# ProDoc_Sensor_2025-09-14.net
KiCad netlist of a schematic drawn in EasyEDA Pro
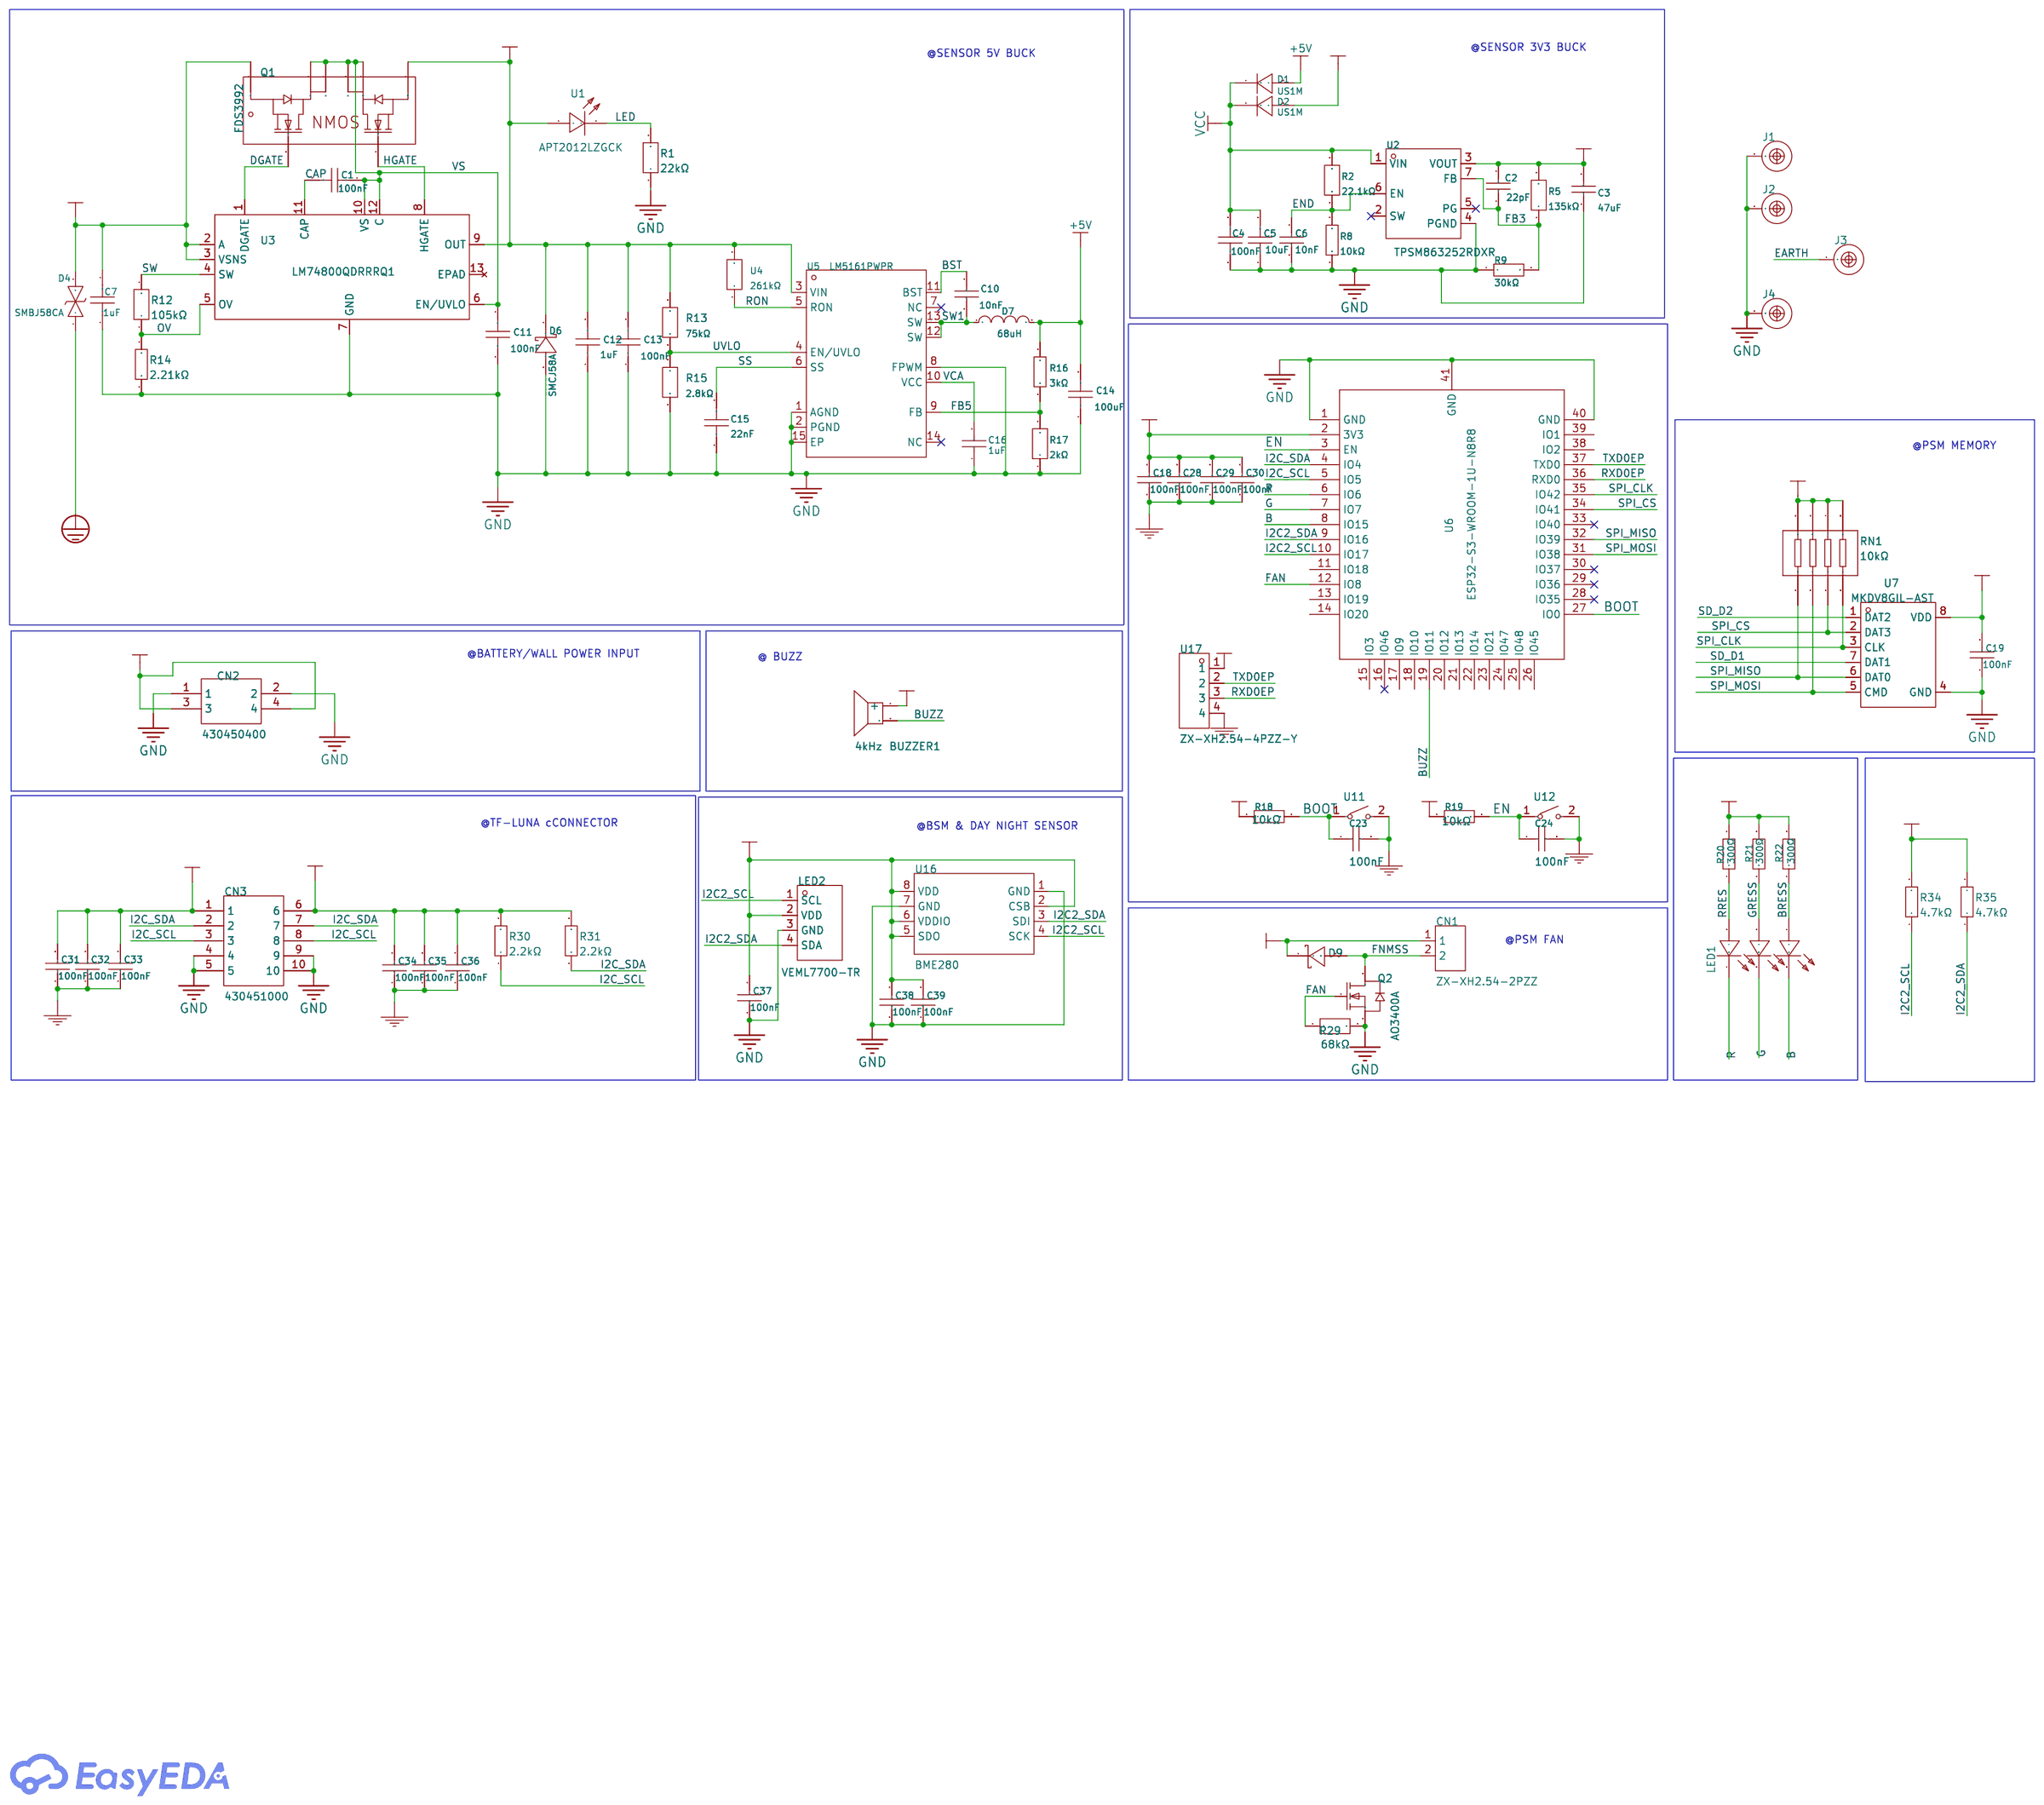
[diagram p0: schematic sheet]

(export (version "E")
  (design (tool "Eeschema 10.0.6"))
  (components
    (comp (ref "BUZZER1")
      (value "4kHz")
      (footprint "easyedapro:BUZ-TH_PKM13EPYH4002-B0")
      (fields
        (field (name "Manufacturer Part") "PKM13EPYH4002-B0")
        (field (name "Manufacturer") "muRata(村田)")
      )
      (libsource (lib "easyedapro") (part "PKM13EPYH4002-B0"))
    )
    (comp (ref "C1")
      (value "100nF")
      (footprint "easyedapro:C1210")
      (fields
        (field (name "Manufacturer Part") "CC1210KKX7RYBB104")
        (field (name "Manufacturer") "YAGEO(国巨)")
      )
      (libsource (lib "easyedapro") (part "CC1210KKX7RYBB104"))
    )
    (comp (ref "C2")
      (value "22pF")
      (footprint "easyedapro:C0201")
      (fields
        (field (name "Manufacturer Part") "GRM0335C1E220JA01D")
        (field (name "Manufacturer") "muRata(村田)")
      )
      (libsource (lib "easyedapro") (part "GRM0335C1E220JA01D"))
    )
    (comp (ref "C3")
      (value "47uF")
      (footprint "easyedapro:C1210")
      (fields
        (field (name "Manufacturer Part") "GRM32ER71A476KE15L")
        (field (name "Manufacturer") "muRata(村田)")
      )
      (libsource (lib "easyedapro") (part "GRM32ER71A476KE15L"))
    )
    (comp (ref "C4")
      (value "100nF")
      (footprint "easyedapro:C0402")
      (fields
        (field (name "Manufacturer Part") "GRM155R71A104KA01D")
        (field (name "Manufacturer") "muRata(村田)")
      )
      (libsource (lib "easyedapro") (part "GRM155R71A104KA01D"))
    )
    (comp (ref "C5")
      (value "10uF")
      (footprint "easyedapro:C0805")
      (fields (field (name "Manufacturer Part") "C0805C106K8PACTU") (field (name "Manufacturer") "KEMET(基美)"))
      (libsource (lib "easyedapro") (part "C0805C106K8PACTU"))
    )
    (comp (ref "C6")
      (value "10nF")
      (footprint "easyedapro:C0201")
      (fields
        (field (name "Manufacturer Part") "GRM033R70J103KA01D")
        (field (name "Manufacturer") "muRata(村田)")
      )
      (libsource (lib "easyedapro") (part "GRM033R70J103KA01D"))
    )
    (comp (ref "C7")
      (value "1uF")
      (footprint "easyedapro:C2220")
      (fields
        (field (name "Manufacturer Part") "GRM55DR72E105KW01L")
        (field (name "Manufacturer") "muRata(村田)")
      )
      (libsource (lib "easyedapro") (part "GRM55DR72E105KW01L"))
    )
    (comp (ref "C10")
      (value "10nF")
      (footprint "easyedapro:C0402")
      (fields
        (field (name "Manufacturer Part") "GRM155R71H103KA88D")
        (field (name "Manufacturer") "muRata(村田)")
      )
      (libsource (lib "easyedapro") (part "GRM155R71H103KA88D"))
    )
    (comp (ref "C11")
      (value "100nF")
      (footprint "easyedapro:C1210")
      (fields
        (field (name "Manufacturer Part") "CC1210KKX7RYBB104")
        (field (name "Manufacturer") "YAGEO(国巨)")
      )
      (libsource (lib "easyedapro") (part "CC1210KKX7RYBB104"))
    )
    (comp (ref "C12")
      (value "1uF")
      (footprint "easyedapro:C2220")
      (fields
        (field (name "Manufacturer Part") "GRM55DR72E105KW01L")
        (field (name "Manufacturer") "muRata(村田)")
      )
      (libsource (lib "easyedapro") (part "GRM55DR72E105KW01L"))
    )
    (comp (ref "C13")
      (value "100nF")
      (footprint "easyedapro:C1210")
      (fields
        (field (name "Manufacturer Part") "CC1210KKX7RYBB104")
        (field (name "Manufacturer") "YAGEO(国巨)")
      )
      (libsource (lib "easyedapro") (part "CC1210KKX7RYBB104"))
    )
    (comp (ref "C14")
      (value "100uF")
      (footprint "easyedapro:C1210")
      (fields
        (field (name "Manufacturer Part") "GRM32ER60J107ME20L")
        (field (name "Manufacturer") "muRata(村田)")
      )
      (libsource (lib "easyedapro") (part "GRM32ER60J107ME20L"))
    )
    (comp (ref "C15")
      (value "22nF")
      (footprint "easyedapro:C0805")
      (fields
        (field (name "Manufacturer Part") "CC0805KRX7R7BB223")
        (field (name "Manufacturer") "YAGEO(国巨)")
      )
      (libsource (lib "easyedapro") (part "CC0805KRX7R7BB223"))
    )
    (comp (ref "C16")
      (value "1uF")
      (footprint "easyedapro:C0603")
      (description "Capacitance:1uF Tolerance:±10% Tolerance:±10% Voltage Rating:16V Temperature Coefficient:X7R")
      (fields
        (field (name "Manufacturer Part") "EMK107B7105KA-T")
        (field (name "Manufacturer") "TAIYO YUDEN(太诱)")
      )
      (libsource (lib "easyedapro") (part "EMK107B7105KA-T"))
    )
    (comp (ref "C18")
      (value "100nF")
      (footprint "easyedapro:C0805")
      (fields (field (name "Manufacturer Part") "0805B104K500NT") (field (name "Manufacturer") "FH(风华)"))
      (libsource (lib "easyedapro") (part "0805B104K500NT"))
    )
    (comp (ref "C19")
      (value "100nF")
      (footprint "easyedapro:C0805")
      (fields (field (name "Manufacturer Part") "0805B104K500NT") (field (name "Manufacturer") "FH(风华)"))
      (libsource (lib "easyedapro") (part "0805B104K500NT"))
    )
    (comp (ref "C23")
      (value "100nF")
      (footprint "easyedapro:C0805")
      (fields (field (name "Manufacturer Part") "0805B104K500NT") (field (name "Manufacturer") "FH(风华)"))
      (libsource (lib "easyedapro") (part "0805B104K500NT"))
    )
    (comp (ref "C24")
      (value "100nF")
      (footprint "easyedapro:C0805")
      (fields (field (name "Manufacturer Part") "0805B104K500NT") (field (name "Manufacturer") "FH(风华)"))
      (libsource (lib "easyedapro") (part "0805B104K500NT"))
    )
    (comp (ref "C28")
      (value "100nF")
      (footprint "easyedapro:C0805")
      (fields (field (name "Manufacturer Part") "0805B104K500NT") (field (name "Manufacturer") "FH(风华)"))
      (libsource (lib "easyedapro") (part "0805B104K500NT"))
    )
    (comp (ref "C29")
      (value "100nF")
      (footprint "easyedapro:C0805")
      (fields (field (name "Manufacturer Part") "0805B104K500NT") (field (name "Manufacturer") "FH(风华)"))
      (libsource (lib "easyedapro") (part "0805B104K500NT"))
    )
    (comp (ref "C30")
      (value "100nF")
      (footprint "easyedapro:C0805")
      (fields (field (name "Manufacturer Part") "0805B104K500NT") (field (name "Manufacturer") "FH(风华)"))
      (libsource (lib "easyedapro") (part "0805B104K500NT"))
    )
    (comp (ref "C31")
      (value "100nF")
      (footprint "easyedapro:C0805")
      (fields (field (name "Manufacturer Part") "0805B104K500NT") (field (name "Manufacturer") "FH(风华)"))
      (libsource (lib "easyedapro") (part "0805B104K500NT"))
    )
    (comp (ref "C32")
      (value "100nF")
      (footprint "easyedapro:C0805")
      (fields (field (name "Manufacturer Part") "0805B104K500NT") (field (name "Manufacturer") "FH(风华)"))
      (libsource (lib "easyedapro") (part "0805B104K500NT"))
    )
    (comp (ref "C33")
      (value "100nF")
      (footprint "easyedapro:C0805")
      (fields (field (name "Manufacturer Part") "0805B104K500NT") (field (name "Manufacturer") "FH(风华)"))
      (libsource (lib "easyedapro") (part "0805B104K500NT"))
    )
    (comp (ref "C34")
      (value "100nF")
      (footprint "easyedapro:C0805")
      (fields (field (name "Manufacturer Part") "0805B104K500NT") (field (name "Manufacturer") "FH(风华)"))
      (libsource (lib "easyedapro") (part "0805B104K500NT"))
    )
    (comp (ref "C35")
      (value "100nF")
      (footprint "easyedapro:C0805")
      (fields (field (name "Manufacturer Part") "0805B104K500NT") (field (name "Manufacturer") "FH(风华)"))
      (libsource (lib "easyedapro") (part "0805B104K500NT"))
    )
    (comp (ref "C36")
      (value "100nF")
      (footprint "easyedapro:C0805")
      (fields (field (name "Manufacturer Part") "0805B104K500NT") (field (name "Manufacturer") "FH(风华)"))
      (libsource (lib "easyedapro") (part "0805B104K500NT"))
    )
    (comp (ref "C37")
      (value "100nF")
      (footprint "easyedapro:C0805")
      (fields (field (name "Manufacturer Part") "0805B104K500NT") (field (name "Manufacturer") "FH(风华)"))
      (libsource (lib "easyedapro") (part "0805B104K500NT"))
    )
    (comp (ref "C38")
      (value "100nF")
      (footprint "easyedapro:C0805")
      (fields (field (name "Manufacturer Part") "0805B104K500NT") (field (name "Manufacturer") "FH(风华)"))
      (libsource (lib "easyedapro") (part "0805B104K500NT"))
    )
    (comp (ref "C39")
      (value "100nF")
      (footprint "easyedapro:C0805")
      (fields (field (name "Manufacturer Part") "0805B104K500NT") (field (name "Manufacturer") "FH(风华)"))
      (libsource (lib "easyedapro") (part "0805B104K500NT"))
    )
    (comp (ref "CN1")
      (value "ZX-XH2.54-2PZZ")
      (footprint "easyedapro:CONN-TH_2P-P2.50_HX25003-2A")
      (fields (field (name "Manufacturer") "Megastar(兆星)"))
      (libsource (lib "easyedapro") (part "ZX-XH2.54-2PZZ"))
    )
    (comp (ref "CN2")
      (value "430450400")
      (footprint "easyedapro:CONN-TH_0430450400")
      (fields (field (name "Manufacturer") "MOLEX"))
      (libsource (lib "easyedapro") (part "0430450400"))
    )
    (comp (ref "CN3")
      (value "430451000")
      (footprint "easyedapro:CONN-TH_43045-1000")
      (fields (field (name "Manufacturer") "MOLEX"))
      (libsource (lib "easyedapro") (part "0430451000"))
    )
    (comp (ref "D1")
      (value "US1M")
      (footprint "easyedapro:SMA_L4.4-W2.8-LS5.4-RD")
      (fields (field (name "Manufacturer") "MDD(辰达半导体)"))
      (libsource (lib "easyedapro") (part "US1MG_C412437"))
    )
    (comp (ref "D2")
      (value "US1M")
      (footprint "easyedapro:SMA_L4.4-W2.8-LS5.4-RD")
      (fields (field (name "Manufacturer") "MDD(辰达半导体)"))
      (libsource (lib "easyedapro") (part "US1MG_C412437"))
    )
    (comp (ref "D4")
      (value "SMBJ58CA")
      (footprint "easyedapro:SMB_L4.6-W3.6-LS5.3-BI")
      (fields (field (name "Manufacturer") "AnBon(安邦)"))
      (libsource (lib "easyedapro") (part "SMBJ58CA_C440309"))
    )
    (comp (ref "D6")
      (value "SMCJ58A")
      (footprint "easyedapro:SMC_L6.9-W5.8-LS7.9-RD")
      (fields (field (name "Manufacturer") "宏嘉诚"))
      (libsource (lib "easyedapro") (part "SMCJ58A_C42371547"))
    )
    (comp (ref "D7")
      (value "68uH")
      (footprint "easyedapro:IND-SMD_L12.5-W12.5-SRR1280-150M")
      (fields (field (name "Manufacturer Part") "SRR1260-680M") (field (name "Manufacturer") "BOURNS"))
      (libsource (lib "easyedapro") (part "SRR1260-680M"))
    )
    (comp (ref "D9")
      (value "BAT46WJ,115")
      (footprint "easyedapro:SOD-323F_L2.0-W1.6-LS2.5-RD")
      (fields (field (name "Manufacturer") "Nexperia(安世)"))
      (libsource (lib "easyedapro") (part "BAT46WJ,115"))
    )
    (comp (ref "J1")
      (value "SCREW-MOUNTING-HOLE-3MM")
      (libsource (lib "easyedapro") (part "SCREW-MOUNTING-HOLE-3MM"))
    )
    (comp (ref "J2")
      (value "SCREW-MOUNTING-HOLE-3MM")
      (libsource (lib "easyedapro") (part "SCREW-MOUNTING-HOLE-3MM"))
    )
    (comp (ref "J3")
      (value "SCREW-MOUNTING-HOLE-3MM")
      (libsource (lib "easyedapro") (part "SCREW-MOUNTING-HOLE-3MM"))
    )
    (comp (ref "J4")
      (value "SCREW-MOUNTING-HOLE-3MM")
      (libsource (lib "easyedapro") (part "SCREW-MOUNTING-HOLE-3MM"))
    )
    (comp (ref "LED1")
      (value "HL-AF-5060H271BU46FU79GC-S1-THL")
      (footprint "easyedapro:LED-ARRAY-SMD_6P-L5.4-W5.0-TL-FD")
      (fields (field (name "Manufacturer") "HONGLITRONIC(鸿利光电)"))
      (libsource (lib "easyedapro") (part "HL-AF-5060H271BU46FU79GC-S1-THL"))
    )
    (comp (ref "LED2")
      (value "VEML7700-TR")
      (footprint "easyedapro:LED-SMD_4P-L6.8-W2.4_VEML7700-TR")
      (fields (field (name "Manufacturer") "VISHAY(威世)"))
      (libsource (lib "easyedapro") (part "VEML7700-TR"))
    )
    (comp (ref "Q1")
      (value "FDS3992")
      (footprint "easyedapro:SO-8_L4.9-W3.9-P1.27-LS5.9-BL")
      (fields (field (name "Manufacturer") "onsemi(安森美)"))
      (libsource (lib "easyedapro") (part "FDS3992"))
    )
    (comp (ref "Q2")
      (value "AO3400A")
      (footprint "easyedapro:SOT-23-3_L2.9-W1.6-P1.90-LS2.8-BR")
      (fields (field (name "Manufacturer") "MSKSEMI(美森科)"))
      (libsource (lib "easyedapro") (part "AO3400A_C5379092"))
    )
    (comp (ref "R1")
      (value "22kΩ")
      (footprint "easyedapro:R1210")
      (fields (field (name "Manufacturer Part") "AC1210FR-0722KL") (field (name "Manufacturer") "YAGEO(国巨)"))
      (libsource (lib "easyedapro") (part "AC1210FR-0722KL"))
    )
    (comp (ref "R2")
      (value "22.1kΩ")
      (footprint "easyedapro:R0402")
      (fields
        (field (name "Manufacturer Part") "CRCW040222K1FKED")
        (field (name "Manufacturer") "VISHAY(威世)")
      )
      (libsource (lib "easyedapro") (part "CRCW040222K1FKED"))
    )
    (comp (ref "R5")
      (value "135kΩ")
      (footprint "easyedapro:R0603")
      (fields (field (name "Manufacturer Part") "RT0603BRD07135KL") (field (name "Manufacturer") "YAGEO(国巨)"))
      (libsource (lib "easyedapro") (part "RT0603BRD07135KL"))
    )
    (comp (ref "R8")
      (value "10kΩ")
      (footprint "easyedapro:R0402")
      (fields
        (field (name "Manufacturer Part") "CRCW040210K0FKED")
        (field (name "Manufacturer") "VISHAY(威世)")
      )
      (libsource (lib "easyedapro") (part "CRCW040210K0FKED"))
    )
    (comp (ref "R9")
      (value "30kΩ")
      (footprint "easyedapro:R0603")
      (fields (field (name "Manufacturer Part") "RC0603FR-0730KL") (field (name "Manufacturer") "YAGEO(国巨)"))
      (libsource (lib "easyedapro") (part "RC0603FR-0730KL"))
    )
    (comp (ref "R12")
      (value "105kΩ")
      (footprint "easyedapro:R1206")
      (fields (field (name "Manufacturer Part") "RC1206FR-07105KL") (field (name "Manufacturer") "YAGEO(国巨)"))
      (libsource (lib "easyedapro") (part "RC1206FR-07105KL"))
    )
    (comp (ref "R13")
      (value "75kΩ")
      (footprint "easyedapro:R1210")
      (fields (field (name "Manufacturer Part") "AC1210FR-0775KL") (field (name "Manufacturer") "YAGEO(国巨)"))
      (libsource (lib "easyedapro") (part "AC1210FR-0775KL"))
    )
    (comp (ref "R14")
      (value "2.21kΩ")
      (footprint "easyedapro:R1206")
      (fields (field (name "Manufacturer Part") "AC1206FR-072K21L") (field (name "Manufacturer") "YAGEO(国巨)"))
      (libsource (lib "easyedapro") (part "AC1206FR-072K21L"))
    )
    (comp (ref "R15")
      (value "2.8kΩ")
      (footprint "easyedapro:R1210")
      (fields (field (name "Manufacturer Part") "AC1210FR-072K8L") (field (name "Manufacturer") "YAGEO(国巨)"))
      (libsource (lib "easyedapro") (part "AC1210FR-072K8L"))
    )
    (comp (ref "R16")
      (value "3kΩ")
      (footprint "easyedapro:R0603")
      (fields (field (name "Manufacturer Part") "RC0603FR-073KL") (field (name "Manufacturer") "YAGEO(国巨)"))
      (libsource (lib "easyedapro") (part "RC0603FR-073KL"))
    )
    (comp (ref "R17")
      (value "2kΩ")
      (footprint "easyedapro:R0402")
      (fields
        (field (name "Manufacturer Part") "CRCW04022K00FKED")
        (field (name "Manufacturer") "VISHAY(威世)")
      )
      (libsource (lib "easyedapro") (part "CRCW04022K00FKED"))
    )
    (comp (ref "R18")
      (value "10kΩ")
      (footprint "easyedapro:R0805")
      (fields
        (field (name "Manufacturer Part") "0805W8F1002T5E")
        (field (name "Manufacturer") "UNI-ROYAL(厚声)")
      )
      (libsource (lib "easyedapro") (part "0805W8F1002T5E"))
    )
    (comp (ref "R19")
      (value "10kΩ")
      (footprint "easyedapro:R0805")
      (fields
        (field (name "Manufacturer Part") "0805W8F1002T5E")
        (field (name "Manufacturer") "UNI-ROYAL(厚声)")
      )
      (libsource (lib "easyedapro") (part "0805W8F1002T5E"))
    )
    (comp (ref "R20")
      (value "300Ω")
      (footprint "easyedapro:R0805")
      (fields
        (field (name "Manufacturer Part") "0805W8F3000T5E")
        (field (name "Manufacturer") "UNI-ROYAL(厚声)")
      )
      (libsource (lib "easyedapro") (part "0805W8F3000T5E"))
    )
    (comp (ref "R21")
      (value "300Ω")
      (footprint "easyedapro:R0805")
      (fields
        (field (name "Manufacturer Part") "0805W8F3000T5E")
        (field (name "Manufacturer") "UNI-ROYAL(厚声)")
      )
      (libsource (lib "easyedapro") (part "0805W8F3000T5E"))
    )
    (comp (ref "R22")
      (value "300Ω")
      (footprint "easyedapro:R0805")
      (fields
        (field (name "Manufacturer Part") "0805W8F3000T5E")
        (field (name "Manufacturer") "UNI-ROYAL(厚声)")
      )
      (libsource (lib "easyedapro") (part "0805W8F3000T5E"))
    )
    (comp (ref "R29")
      (value "68kΩ")
      (footprint "easyedapro:R1206")
      (fields (field (name "Manufacturer Part") "RT1206BRD0768KL") (field (name "Manufacturer") "YAGEO(国巨)"))
      (libsource (lib "easyedapro") (part "RT1206BRD0768KL"))
    )
    (comp (ref "R30")
      (value "2.2kΩ")
      (footprint "easyedapro:R0805")
      (fields
        (field (name "Manufacturer Part") "0805W8F2201T5E")
        (field (name "Manufacturer") "UNI-ROYAL(厚声)")
      )
      (libsource (lib "easyedapro") (part "0805W8F2201T5E"))
    )
    (comp (ref "R31")
      (value "2.2kΩ")
      (footprint "easyedapro:R0805")
      (fields
        (field (name "Manufacturer Part") "0805W8F2201T5E")
        (field (name "Manufacturer") "UNI-ROYAL(厚声)")
      )
      (libsource (lib "easyedapro") (part "0805W8F2201T5E"))
    )
    (comp (ref "R34")
      (value "4.7kΩ")
      (footprint "easyedapro:R0805")
      (fields
        (field (name "Manufacturer Part") "0805W8F4701T5E")
        (field (name "Manufacturer") "UNI-ROYAL(厚声)")
      )
      (libsource (lib "easyedapro") (part "0805W8F4701T5E"))
    )
    (comp (ref "R35")
      (value "4.7kΩ")
      (footprint "easyedapro:R0805")
      (fields
        (field (name "Manufacturer Part") "0805W8F4701T5E")
        (field (name "Manufacturer") "UNI-ROYAL(厚声)")
      )
      (libsource (lib "easyedapro") (part "0805W8F4701T5E"))
    )
    (comp (ref "RN1")
      (value "10kΩ")
      (footprint "easyedapro:RES-ARRAY-SMD_0603-8P-L3.2-W1.6-BL")
      (fields
        (field (name "Manufacturer Part") "4D03WGJ0103T5E")
        (field (name "Manufacturer") "UNI-ROYAL(厚声)")
      )
      (libsource (lib "easyedapro") (part "4D03WGJ0103T5E"))
    )
    (comp (ref "U1")
      (value "APT2012LZGCK")
      (footprint "easyedapro:LED-SMD_L2.0-W1.3-R-RD")
      (fields (field (name "Manufacturer") "Kingbright"))
      (libsource (lib "easyedapro") (part "APT2012LZGCK"))
    )
    (comp (ref "U2")
      (value "TPSM863252RDXR")
      (footprint "easyedapro:QFN-7_L4.0-W3.3_TPSM863257RDXR")
      (fields (field (name "Manufacturer") "TI(德州仪器)"))
      (libsource (lib "easyedapro") (part "TPSM863252RDXR"))
    )
    (comp (ref "U3")
      (value "LM74800QDRRRQ1")
      (footprint "easyedapro:WSON-12_L3.0-W3.0-P0.50-TL-EP-2")
      (fields (field (name "Manufacturer") "TI(德州仪器)"))
      (libsource (lib "easyedapro") (part "LM74800QDRRRQ1"))
    )
    (comp (ref "U4")
      (value "261kΩ")
      (footprint "easyedapro:R0402")
      (fields
        (field (name "Manufacturer Part") "CRCW0402261KFKED")
        (field (name "Manufacturer") "VISHAY(威世)")
      )
      (libsource (lib "easyedapro") (part "CRCW0402261KFKED"))
    )
    (comp (ref "U5")
      (value "LM5161PWPR")
      (footprint "easyedapro:HTSSOP-14_L5.0-W4.4-P0.65-LS6.4-BL-EP3.0")
      (fields (field (name "Manufacturer") "TI(德州仪器)"))
      (libsource (lib "easyedapro") (part "LM5161PWPR"))
    )
    (comp (ref "U6")
      (value "ESP32-S3-WROOM-1U-N8R8")
      (footprint "easyedapro:WIRELM-SMD_ESP32-S3-WROOM-1U")
      (fields (field (name "Manufacturer") "ESPRESSIF(乐鑫)"))
      (libsource (lib "easyedapro") (part "ESP32-S3-WROOM-1U-N8R8"))
    )
    (comp (ref "U7")
      (value "MKDV8GIL-AST")
      (footprint "easyedapro:LGA-8_L6.0-W8.0-P1.27-TL")
      (fields (field (name "Manufacturer") "MK(米客方德)"))
      (libsource (lib "easyedapro") (part "MKDV8GIL-AST"))
    )
    (comp (ref "U11") (value "TD-1183SN-1.7H-250") (libsource (lib "easyedapro") (part "TD-1183SN-1.7H-250")))
    (comp (ref "U12") (value "TD-1183SN-1.7H-250") (libsource (lib "easyedapro") (part "TD-1183SN-1.7H-250")))
    (comp (ref "U16")
      (value "BME280")
      (footprint "easyedapro:LGA-8_BME280_BL")
      (description "Voltage - Supply:1.71V~3.6V Voltage - Supply:1.71V~3.6V")
      (fields (field (name "Manufacturer") "Bosch(博世)"))
      (libsource (lib "easyedapro") (part "BME280"))
    )
    (comp (ref "U17")
      (value "ZX-XH2.54-4PZZ-Y")
      (footprint "easyedapro:CONN-TH_4P-P2.50_ZX-XH2.54-4PZZ-Y")
      (fields (field (name "Manufacturer") "Megastar(兆星)"))
      (libsource (lib "easyedapro") (part "ZX-XH2.54-4PZZ-Y"))
    )
  )
  (nets
    (net (code "1") (name "+3V3") (class "Default")
      (node (ref "BUZZER1") (pin "1") (pinfunction "+_1") (pintype "unspecified"))
      (node (ref "C18") (pin "2") (pinfunction "2_2") (pintype "input"))
      (node (ref "C19") (pin "2") (pinfunction "2_2") (pintype "input"))
      (node (ref "C2") (pin "2") (pinfunction "2_2") (pintype "input"))
      (node (ref "C28") (pin "2") (pinfunction "2_2") (pintype "input"))
      (node (ref "C29") (pin "2") (pinfunction "2_2") (pintype "input"))
      (node (ref "C3") (pin "2") (pinfunction "2_2") (pintype "input"))
      (node (ref "C30") (pin "2") (pinfunction "2_2") (pintype "input"))
      (node (ref "C31") (pin "2") (pinfunction "2_2") (pintype "input"))
      (node (ref "C32") (pin "2") (pinfunction "2_2") (pintype "input"))
      (node (ref "C33") (pin "2") (pinfunction "2_2") (pintype "input"))
      (node (ref "C34") (pin "2") (pinfunction "2_2") (pintype "input"))
      (node (ref "C35") (pin "2") (pinfunction "2_2") (pintype "input"))
      (node (ref "C36") (pin "2") (pinfunction "2_2") (pintype "input"))
      (node (ref "C37") (pin "2") (pinfunction "2_2") (pintype "input"))
      (node (ref "C38") (pin "2") (pinfunction "2_2") (pintype "input"))
      (node (ref "C39") (pin "2") (pinfunction "2_2") (pintype "input"))
      (node (ref "CN3") (pin "1") (pinfunction "1_1") (pintype "unspecified"))
      (node (ref "CN3") (pin "6") (pinfunction "6_6") (pintype "unspecified"))
      (node (ref "LED2") (pin "2") (pinfunction "VDD_2") (pintype "unspecified"))
      (node (ref "R18") (pin "1") (pinfunction "1_1") (pintype "input"))
      (node (ref "R19") (pin "1") (pinfunction "1_1") (pintype "input"))
      (node (ref "R20") (pin "2") (pinfunction "2_2") (pintype "input"))
      (node (ref "R21") (pin "2") (pinfunction "2_2") (pintype "input"))
      (node (ref "R22") (pin "2") (pinfunction "2_2") (pintype "input"))
      (node (ref "R30") (pin "2") (pinfunction "2_2") (pintype "input"))
      (node (ref "R31") (pin "2") (pinfunction "2_2") (pintype "input"))
      (node (ref "R34") (pin "2") (pinfunction "2_2") (pintype "input"))
      (node (ref "R35") (pin "2") (pinfunction "2_2") (pintype "input"))
      (node (ref "R5") (pin "2") (pinfunction "2_2") (pintype "unspecified"))
      (node (ref "RN1") (pin "5") (pinfunction "5_5") (pintype "input"))
      (node (ref "RN1") (pin "6") (pinfunction "6_6") (pintype "input"))
      (node (ref "RN1") (pin "7") (pinfunction "7_7") (pintype "input"))
      (node (ref "RN1") (pin "8") (pinfunction "8_8") (pintype "input"))
      (node (ref "U16") (pin "2") (pinfunction "CSB_2") (pintype "unspecified"))
      (node (ref "U16") (pin "5") (pinfunction "SDO_5") (pintype "unspecified"))
      (node (ref "U16") (pin "6") (pinfunction "VDDIO_6") (pintype "unspecified"))
      (node (ref "U16") (pin "8") (pinfunction "VDD_8") (pintype "unspecified"))
      (node (ref "U17") (pin "1") (pinfunction "1_1") (pintype "unspecified"))
      (node (ref "U2") (pin "3") (pinfunction "VOUT_3") (pintype "unspecified"))
      (node (ref "U6") (pin "2") (pinfunction "3V3_2") (pintype "unspecified"))
      (node (ref "U7") (pin "8") (pinfunction "VDD_8") (pintype "unspecified"))
    )
    (net (code "2") (name "+5V") (class "Default")
      (node (ref "C14") (pin "2") (pinfunction "2_2") (pintype "input"))
      (node (ref "D1") (pin "2") (pinfunction "A_2") (pintype "unspecified"))
      (node (ref "D7") (pin "2") (pinfunction "2_2") (pintype "unspecified"))
      (node (ref "R16") (pin "2") (pinfunction "2_2") (pintype "input"))
    )
    (net (code "3") (name "+48V") (class "Default")
      (node (ref "C12") (pin "2") (pinfunction "2_2") (pintype "input"))
      (node (ref "C13") (pin "2") (pinfunction "2_2") (pintype "unspecified"))
      (node (ref "D6") (pin "1") (pinfunction "K_1") (pintype "unspecified"))
      (node (ref "Q1") (pin "3") (pinfunction "S2_3") (pintype "unspecified"))
      (node (ref "R13") (pin "2") (pinfunction "2_2") (pintype "input"))
      (node (ref "U1") (pin "1") (pinfunction "A_1") (pintype "unspecified"))
      (node (ref "U3") (pin "9") (pinfunction "OUT_9") (pintype "unspecified"))
      (node (ref "U4") (pin "2") (pinfunction "2_2") (pintype "unspecified"))
      (node (ref "U5") (pin "3") (pinfunction "VIN_3") (pintype "unspecified"))
    )
    (net (code "4") (name "/B") (class "Default")
      (node (ref "LED1") (pin "6") (pinfunction "C_6") (pintype "unspecified"))
      (node (ref "U6") (pin "8") (pinfunction "IO15_8") (pintype "unspecified"))
    )
    (net (code "5") (name "/BOOT") (class "Default")
      (node (ref "C23") (pin "1") (pinfunction "1_1") (pintype "input"))
      (node (ref "R18") (pin "2") (pinfunction "2_2") (pintype "input"))
      (node (ref "U11") (pin "1") (pinfunction "1_1") (pintype "unspecified"))
      (node (ref "U6") (pin "27") (pinfunction "IO0_27") (pintype "unspecified"))
    )
    (net (code "6") (name "/BRESS") (class "Default")
      (node (ref "LED1") (pin "1") (pinfunction "A_1") (pintype "unspecified"))
      (node (ref "R22") (pin "1") (pinfunction "1_1") (pintype "input"))
    )
    (net (code "7") (name "/BST") (class "Default")
      (node (ref "C10") (pin "2") (pinfunction "2_2") (pintype "input"))
      (node (ref "U5") (pin "11") (pinfunction "BST_11") (pintype "unspecified"))
    )
    (net (code "8") (name "/BUZZ") (class "Default")
      (node (ref "BUZZER1") (pin "2") (pinfunction "2_2") (pintype "unspecified"))
      (node (ref "U6") (pin "19") (pinfunction "IO11_19") (pintype "unspecified"))
    )
    (net (code "9") (name "/CAP") (class "Default")
      (node (ref "C1") (pin "2") (pinfunction "2_2") (pintype "unspecified"))
      (node (ref "U3") (pin "11") (pinfunction "CAP_11") (pintype "unspecified"))
    )
    (net (code "10") (name "/DGATE") (class "Default")
      (node (ref "Q1") (pin "2") (pinfunction "G1_2") (pintype "unspecified"))
      (node (ref "U3") (pin "1") (pinfunction "DGATE_1") (pintype "unspecified"))
    )
    (net (code "11") (name "/EN") (class "Default")
      (node (ref "C24") (pin "1") (pinfunction "1_1") (pintype "input"))
      (node (ref "R19") (pin "2") (pinfunction "2_2") (pintype "input"))
      (node (ref "U12") (pin "1") (pinfunction "1_1") (pintype "unspecified"))
      (node (ref "U6") (pin "3") (pinfunction "EN_3") (pintype "unspecified"))
    )
    (net (code "12") (name "/END") (class "Default")
      (node (ref "C6") (pin "2") (pinfunction "2_2") (pintype "input"))
      (node (ref "R2") (pin "1") (pinfunction "1_1") (pintype "unspecified"))
      (node (ref "R8") (pin "2") (pinfunction "2_2") (pintype "unspecified"))
      (node (ref "U2") (pin "6") (pinfunction "EN_6") (pintype "unspecified"))
    )
    (net (code "13") (name "/FAN") (class "Default")
      (node (ref "Q2") (pin "1") (pinfunction "G_1") (pintype "unspecified"))
      (node (ref "R29") (pin "1") (pinfunction "1_1") (pintype "unspecified"))
      (node (ref "U6") (pin "12") (pinfunction "IO8_12") (pintype "unspecified"))
    )
    (net (code "14") (name "/FB3") (class "Default")
      (node (ref "C2") (pin "1") (pinfunction "1_1") (pintype "input"))
      (node (ref "R5") (pin "1") (pinfunction "1_1") (pintype "unspecified"))
      (node (ref "R9") (pin "2") (pinfunction "2_2") (pintype "input"))
      (node (ref "U2") (pin "7") (pinfunction "FB_7") (pintype "unspecified"))
    )
    (net (code "15") (name "/FB5") (class "Default")
      (node (ref "R16") (pin "1") (pinfunction "1_1") (pintype "input"))
      (node (ref "R17") (pin "2") (pinfunction "2_2") (pintype "input"))
      (node (ref "U5") (pin "9") (pinfunction "FB_9") (pintype "unspecified"))
    )
    (net (code "16") (name "/FNMSS") (class "Default")
      (node (ref "CN1") (pin "2") (pinfunction "2_2") (pintype "unspecified"))
      (node (ref "D9") (pin "2") (pinfunction "A_2") (pintype "unspecified"))
      (node (ref "Q2") (pin "3") (pinfunction "D_3") (pintype "unspecified"))
    )
    (net (code "17") (name "/G") (class "Default")
      (node (ref "LED1") (pin "5") (pinfunction "C_5") (pintype "unspecified"))
      (node (ref "U6") (pin "7") (pinfunction "IO7_7") (pintype "unspecified"))
    )
    (net (code "18") (name "/GRESS") (class "Default")
      (node (ref "LED1") (pin "2") (pinfunction "A_2") (pintype "unspecified"))
      (node (ref "R21") (pin "1") (pinfunction "1_1") (pintype "input"))
    )
    (net (code "19") (name "/HGATE") (class "Default")
      (node (ref "Q1") (pin "4") (pinfunction "G2_4") (pintype "unspecified"))
      (node (ref "U3") (pin "8") (pinfunction "HGATE_8") (pintype "unspecified"))
    )
    (net (code "20") (name "/I2C2_SCL") (class "Default")
      (node (ref "LED2") (pin "1") (pinfunction "SCL_1") (pintype "unspecified"))
      (node (ref "R34") (pin "1") (pinfunction "1_1") (pintype "input"))
      (node (ref "U16") (pin "4") (pinfunction "SCK_4") (pintype "unspecified"))
      (node (ref "U6") (pin "10") (pinfunction "IO17_10") (pintype "unspecified"))
    )
    (net (code "21") (name "/I2C2_SDA") (class "Default")
      (node (ref "LED2") (pin "4") (pinfunction "SDA_4") (pintype "unspecified"))
      (node (ref "R35") (pin "1") (pinfunction "1_1") (pintype "input"))
      (node (ref "U16") (pin "3") (pinfunction "SDI_3") (pintype "unspecified"))
      (node (ref "U6") (pin "9") (pinfunction "IO16_9") (pintype "unspecified"))
    )
    (net (code "22") (name "/I2C_SCL") (class "Default")
      (node (ref "CN3") (pin "3") (pinfunction "3_3") (pintype "unspecified"))
      (node (ref "CN3") (pin "8") (pinfunction "8_8") (pintype "unspecified"))
      (node (ref "R30") (pin "1") (pinfunction "1_1") (pintype "input"))
      (node (ref "U6") (pin "5") (pinfunction "IO5_5") (pintype "unspecified"))
    )
    (net (code "23") (name "/I2C_SDA") (class "Default")
      (node (ref "CN3") (pin "2") (pinfunction "2_2") (pintype "unspecified"))
      (node (ref "CN3") (pin "7") (pinfunction "7_7") (pintype "unspecified"))
      (node (ref "R31") (pin "1") (pinfunction "1_1") (pintype "input"))
      (node (ref "U6") (pin "4") (pinfunction "IO4_4") (pintype "unspecified"))
    )
    (net (code "24") (name "/LED") (class "Default")
      (node (ref "R1") (pin "2") (pinfunction "2_2") (pintype "unspecified"))
      (node (ref "U1") (pin "2") (pinfunction "K_2") (pintype "unspecified"))
    )
    (net (code "25") (name "/OV") (class "Default")
      (node (ref "R12") (pin "1") (pinfunction "1_1") (pintype "unspecified"))
      (node (ref "R14") (pin "2") (pinfunction "2_2") (pintype "unspecified"))
      (node (ref "U3") (pin "5") (pinfunction "OV_5") (pintype "unspecified"))
    )
    (net (code "26") (name "/R") (class "Default")
      (node (ref "LED1") (pin "4") (pinfunction "C_4") (pintype "unspecified"))
      (node (ref "U6") (pin "6") (pinfunction "IO6_6") (pintype "unspecified"))
    )
    (net (code "27") (name "/RON") (class "Default")
      (node (ref "U4") (pin "1") (pinfunction "1_1") (pintype "unspecified"))
      (node (ref "U5") (pin "5") (pinfunction "RON_5") (pintype "unspecified"))
    )
    (net (code "28") (name "/RRES") (class "Default")
      (node (ref "LED1") (pin "3") (pinfunction "A_3") (pintype "unspecified"))
      (node (ref "R20") (pin "1") (pinfunction "1_1") (pintype "input"))
    )
    (net (code "29") (name "/RXD0EP") (class "Default")
      (node (ref "U17") (pin "3") (pinfunction "3_3") (pintype "unspecified"))
      (node (ref "U6") (pin "36") (pinfunction "RXD0_36") (pintype "unspecified"))
    )
    (net (code "30") (name "/SD_D1") (class "Default")
      (node (ref "U7") (pin "7") (pinfunction "DAT1_7") (pintype "unspecified"))
    )
    (net (code "31") (name "/SD_D2") (class "Default")
      (node (ref "U7") (pin "1") (pinfunction "DAT2_1") (pintype "unspecified"))
    )
    (net (code "32") (name "/SPI_CLK") (class "Default")
      (node (ref "RN1") (pin "1") (pinfunction "1_1") (pintype "input"))
      (node (ref "U6") (pin "35") (pinfunction "IO42_35") (pintype "unspecified"))
      (node (ref "U7") (pin "3") (pinfunction "CLK_3") (pintype "unspecified"))
    )
    (net (code "33") (name "/SPI_CS") (class "Default")
      (node (ref "RN1") (pin "2") (pinfunction "2_2") (pintype "input"))
      (node (ref "U6") (pin "34") (pinfunction "IO41_34") (pintype "unspecified"))
      (node (ref "U7") (pin "2") (pinfunction "DAT3_2") (pintype "unspecified"))
    )
    (net (code "34") (name "/SPI_MISO") (class "Default")
      (node (ref "RN1") (pin "4") (pinfunction "4_4") (pintype "input"))
      (node (ref "U6") (pin "32") (pinfunction "IO39_32") (pintype "unspecified"))
      (node (ref "U7") (pin "6") (pinfunction "DAT0_6") (pintype "unspecified"))
    )
    (net (code "35") (name "/SPI_MOSI") (class "Default")
      (node (ref "RN1") (pin "3") (pinfunction "3_3") (pintype "input"))
      (node (ref "U6") (pin "31") (pinfunction "IO38_31") (pintype "unspecified"))
      (node (ref "U7") (pin "5") (pinfunction "CMD_5") (pintype "unspecified"))
    )
    (net (code "36") (name "/SS") (class "Default")
      (node (ref "C15") (pin "2") (pinfunction "2_2") (pintype "input"))
      (node (ref "U5") (pin "6") (pinfunction "SS_6") (pintype "unspecified"))
    )
    (net (code "37") (name "/SW") (class "Default")
      (node (ref "R12") (pin "2") (pinfunction "2_2") (pintype "unspecified"))
      (node (ref "U3") (pin "4") (pinfunction "SW_4") (pintype "unspecified"))
    )
    (net (code "38") (name "/SW1") (class "Default")
      (node (ref "C10") (pin "1") (pinfunction "1_1") (pintype "input"))
      (node (ref "D7") (pin "1") (pinfunction "1_1") (pintype "unspecified"))
      (node (ref "U5") (pin "12") (pinfunction "SW_12") (pintype "unspecified"))
      (node (ref "U5") (pin "13") (pinfunction "SW_13") (pintype "unspecified"))
    )
    (net (code "39") (name "/TXD0EP") (class "Default")
      (node (ref "U17") (pin "2") (pinfunction "2_2") (pintype "unspecified"))
      (node (ref "U6") (pin "37") (pinfunction "TXD0_37") (pintype "unspecified"))
    )
    (net (code "40") (name "/UVLO") (class "Default")
      (node (ref "R13") (pin "1") (pinfunction "1_1") (pintype "input"))
      (node (ref "R15") (pin "2") (pinfunction "2_2") (pintype "unspecified"))
      (node (ref "U5") (pin "4") (pinfunction "EN/UVLO_4") (pintype "unspecified"))
    )
    (net (code "41") (name "/VCA") (class "Default")
      (node (ref "C16") (pin "2") (pinfunction "2_2") (pintype "input"))
      (node (ref "U5") (pin "10") (pinfunction "VCC_10") (pintype "unspecified"))
    )
    (net (code "42") (name "/VS") (class "Default")
      (node (ref "C1") (pin "1") (pinfunction "1_1") (pintype "unspecified"))
      (node (ref "C11") (pin "2") (pinfunction "2_2") (pintype "unspecified"))
      (node (ref "Q1") (pin "5") (pinfunction "D2_5") (pintype "unspecified"))
      (node (ref "Q1") (pin "6") (pinfunction "D2_6") (pintype "unspecified"))
      (node (ref "Q1") (pin "7") (pinfunction "D1_7") (pintype "unspecified"))
      (node (ref "Q1") (pin "8") (pinfunction "D1_8") (pintype "unspecified"))
      (node (ref "U3") (pin "10") (pinfunction "VS_10") (pintype "unspecified"))
      (node (ref "U3") (pin "12") (pinfunction "C_12") (pintype "unspecified"))
      (node (ref "U3") (pin "6") (pinfunction "EN/UVLO_6") (pintype "unspecified"))
    )
    (net (code "43") (name "EARTH") (class "Default")
      (node (ref "D4") (pin "1") (pinfunction "1_1") (pintype "unspecified"))
      (node (ref "J3") (pin "1") (pinfunction "1_1") (pintype "unspecified"))
    )
    (net (code "44") (name "GND") (class "Default")
      (node (ref "C11") (pin "1") (pinfunction "1_1") (pintype "unspecified"))
      (node (ref "C12") (pin "1") (pinfunction "1_1") (pintype "input"))
      (node (ref "C13") (pin "1") (pinfunction "1_1") (pintype "unspecified"))
      (node (ref "C14") (pin "1") (pinfunction "1_1") (pintype "input"))
      (node (ref "C15") (pin "1") (pinfunction "1_1") (pintype "input"))
      (node (ref "C16") (pin "1") (pinfunction "1_1") (pintype "input"))
      (node (ref "C18") (pin "1") (pinfunction "1_1") (pintype "input"))
      (node (ref "C19") (pin "1") (pinfunction "1_1") (pintype "input"))
      (node (ref "C23") (pin "2") (pinfunction "2_2") (pintype "input"))
      (node (ref "C24") (pin "2") (pinfunction "2_2") (pintype "input"))
      (node (ref "C28") (pin "1") (pinfunction "1_1") (pintype "input"))
      (node (ref "C29") (pin "1") (pinfunction "1_1") (pintype "input"))
      (node (ref "C3") (pin "1") (pinfunction "1_1") (pintype "input"))
      (node (ref "C30") (pin "1") (pinfunction "1_1") (pintype "input"))
      (node (ref "C31") (pin "1") (pinfunction "1_1") (pintype "input"))
      (node (ref "C32") (pin "1") (pinfunction "1_1") (pintype "input"))
      (node (ref "C33") (pin "1") (pinfunction "1_1") (pintype "input"))
      (node (ref "C34") (pin "1") (pinfunction "1_1") (pintype "input"))
      (node (ref "C35") (pin "1") (pinfunction "1_1") (pintype "input"))
      (node (ref "C36") (pin "1") (pinfunction "1_1") (pintype "input"))
      (node (ref "C37") (pin "1") (pinfunction "1_1") (pintype "input"))
      (node (ref "C38") (pin "1") (pinfunction "1_1") (pintype "input"))
      (node (ref "C39") (pin "1") (pinfunction "1_1") (pintype "input"))
      (node (ref "C4") (pin "1") (pinfunction "1_1") (pintype "input"))
      (node (ref "C5") (pin "1") (pinfunction "1_1") (pintype "unspecified"))
      (node (ref "C6") (pin "1") (pinfunction "1_1") (pintype "input"))
      (node (ref "C7") (pin "2") (pinfunction "2_2") (pintype "input"))
      (node (ref "CN2") (pin "1") (pinfunction "1_1") (pintype "unspecified"))
      (node (ref "CN2") (pin "2") (pinfunction "2_2") (pintype "unspecified"))
      (node (ref "CN3") (pin "10") (pinfunction "10_10") (pintype "unspecified"))
      (node (ref "CN3") (pin "4") (pinfunction "4_4") (pintype "unspecified"))
      (node (ref "CN3") (pin "5") (pinfunction "5_5") (pintype "unspecified"))
      (node (ref "CN3") (pin "9") (pinfunction "9_9") (pintype "unspecified"))
      (node (ref "D6") (pin "2") (pinfunction "A_2") (pintype "unspecified"))
      (node (ref "J1") (pin "1") (pinfunction "1_1") (pintype "unspecified"))
      (node (ref "J2") (pin "1") (pinfunction "1_1") (pintype "unspecified"))
      (node (ref "J4") (pin "1") (pinfunction "1_1") (pintype "unspecified"))
      (node (ref "LED2") (pin "3") (pinfunction "GND_3") (pintype "unspecified"))
      (node (ref "Q2") (pin "2") (pinfunction "S_2") (pintype "unspecified"))
      (node (ref "R1") (pin "1") (pinfunction "1_1") (pintype "unspecified"))
      (node (ref "R14") (pin "1") (pinfunction "1_1") (pintype "unspecified"))
      (node (ref "R15") (pin "1") (pinfunction "1_1") (pintype "unspecified"))
      (node (ref "R17") (pin "1") (pinfunction "1_1") (pintype "input"))
      (node (ref "R29") (pin "2") (pinfunction "2_2") (pintype "unspecified"))
      (node (ref "R8") (pin "1") (pinfunction "1_1") (pintype "unspecified"))
      (node (ref "R9") (pin "1") (pinfunction "1_1") (pintype "input"))
      (node (ref "U11") (pin "2") (pinfunction "2_2") (pintype "unspecified"))
      (node (ref "U12") (pin "2") (pinfunction "2_2") (pintype "unspecified"))
      (node (ref "U16") (pin "1") (pinfunction "GND_1") (pintype "unspecified"))
      (node (ref "U16") (pin "7") (pinfunction "GND_7") (pintype "unspecified"))
      (node (ref "U17") (pin "4") (pinfunction "4_4") (pintype "unspecified"))
      (node (ref "U2") (pin "4") (pinfunction "PGND_4") (pintype "unspecified"))
      (node (ref "U3") (pin "7") (pinfunction "GND_7") (pintype "unspecified"))
      (node (ref "U5") (pin "1") (pinfunction "AGND_1") (pintype "unspecified"))
      (node (ref "U5") (pin "15") (pinfunction "EP_15") (pintype "unspecified"))
      (node (ref "U5") (pin "2") (pinfunction "PGND_2") (pintype "unspecified"))
      (node (ref "U5") (pin "8") (pinfunction "FPWM_8") (pintype "unspecified"))
      (node (ref "U6") (pin "1") (pinfunction "GND_1") (pintype "unspecified"))
      (node (ref "U6") (pin "40") (pinfunction "GND_40") (pintype "unspecified"))
      (node (ref "U6") (pin "41") (pinfunction "GND_41") (pintype "unspecified"))
      (node (ref "U7") (pin "4") (pinfunction "GND_4") (pintype "unspecified"))
    )
    (net (code "46") (name "VCC") (class "Default")
      (node (ref "C4") (pin "2") (pinfunction "2_2") (pintype "input"))
      (node (ref "C5") (pin "2") (pinfunction "2_2") (pintype "unspecified"))
      (node (ref "D1") (pin "1") (pinfunction "C_1") (pintype "unspecified"))
      (node (ref "D2") (pin "1") (pinfunction "C_1") (pintype "unspecified"))
      (node (ref "R2") (pin "2") (pinfunction "2_2") (pintype "unspecified"))
      (node (ref "U2") (pin "1") (pinfunction "VIN_1") (pintype "unspecified"))
    )
    (net (code "47") (name "VIN") (class "Default")
      (node (ref "C7") (pin "1") (pinfunction "1_1") (pintype "input"))
      (node (ref "CN1") (pin "1") (pinfunction "1_1") (pintype "unspecified"))
      (node (ref "CN2") (pin "3") (pinfunction "3_3") (pintype "unspecified"))
      (node (ref "CN2") (pin "4") (pinfunction "4_4") (pintype "unspecified"))
      (node (ref "D4") (pin "2") (pinfunction "2_2") (pintype "unspecified"))
      (node (ref "D9") (pin "1") (pinfunction "K_1") (pintype "unspecified"))
      (node (ref "Q1") (pin "1") (pinfunction "S1_1") (pintype "unspecified"))
      (node (ref "U3") (pin "2") (pinfunction "A_2") (pintype "unspecified"))
      (node (ref "U3") (pin "3") (pinfunction "VSNS_3") (pintype "unspecified"))
    )
    (net (code "48") (name "unconnected-(D2-A-Pad2)") (class "Default")
      (node (ref "D2") (pin "2") (pinfunction "A_2") (pintype "unspecified"))
    )
    (net (code "49") (name "unconnected-(U2-PG-Pad5)") (class "Default")
      (node (ref "U2") (pin "5") (pinfunction "PG_5") (pintype "unspecified+no_connect"))
    )
    (net (code "50") (name "unconnected-(U2-SW-Pad2)") (class "Default")
      (node (ref "U2") (pin "2") (pinfunction "SW_2") (pintype "unspecified+no_connect"))
    )
    (net (code "51") (name "unconnected-(U3-EPAD-Pad13)") (class "Default")
      (node (ref "U3") (pin "13") (pinfunction "EPAD_13") (pintype "no_connect"))
    )
    (net (code "52") (name "unconnected-(U5-NC-Pad7)") (class "Default")
      (node (ref "U5") (pin "7") (pinfunction "NC_7") (pintype "unspecified+no_connect"))
    )
    (net (code "53") (name "unconnected-(U5-NC-Pad14)") (class "Default")
      (node (ref "U5") (pin "14") (pinfunction "NC_14") (pintype "unspecified+no_connect"))
    )
    (net (code "54") (name "unconnected-(U6-IO1-Pad39)") (class "Default")
      (node (ref "U6") (pin "39") (pinfunction "IO1_39") (pintype "unspecified"))
    )
    (net (code "55") (name "unconnected-(U6-IO2-Pad38)") (class "Default")
      (node (ref "U6") (pin "38") (pinfunction "IO2_38") (pintype "unspecified"))
    )
    (net (code "56") (name "unconnected-(U6-IO3-Pad15)") (class "Default")
      (node (ref "U6") (pin "15") (pinfunction "IO3_15") (pintype "unspecified"))
    )
    (net (code "57") (name "unconnected-(U6-IO9-Pad17)") (class "Default")
      (node (ref "U6") (pin "17") (pinfunction "IO9_17") (pintype "unspecified"))
    )
    (net (code "58") (name "unconnected-(U6-IO10-Pad18)") (class "Default")
      (node (ref "U6") (pin "18") (pinfunction "IO10_18") (pintype "unspecified"))
    )
    (net (code "59") (name "unconnected-(U6-IO12-Pad20)") (class "Default")
      (node (ref "U6") (pin "20") (pinfunction "IO12_20") (pintype "unspecified"))
    )
    (net (code "60") (name "unconnected-(U6-IO13-Pad21)") (class "Default")
      (node (ref "U6") (pin "21") (pinfunction "IO13_21") (pintype "unspecified"))
    )
    (net (code "61") (name "unconnected-(U6-IO14-Pad22)") (class "Default")
      (node (ref "U6") (pin "22") (pinfunction "IO14_22") (pintype "unspecified"))
    )
    (net (code "62") (name "unconnected-(U6-IO18-Pad11)") (class "Default")
      (node (ref "U6") (pin "11") (pinfunction "IO18_11") (pintype "unspecified"))
    )
    (net (code "63") (name "unconnected-(U6-IO19-Pad13)") (class "Default")
      (node (ref "U6") (pin "13") (pinfunction "IO19_13") (pintype "unspecified"))
    )
    (net (code "64") (name "unconnected-(U6-IO20-Pad14)") (class "Default")
      (node (ref "U6") (pin "14") (pinfunction "IO20_14") (pintype "unspecified"))
    )
    (net (code "65") (name "unconnected-(U6-IO21-Pad23)") (class "Default")
      (node (ref "U6") (pin "23") (pinfunction "IO21_23") (pintype "unspecified"))
    )
    (net (code "66") (name "unconnected-(U6-IO35-Pad28)") (class "Default")
      (node (ref "U6") (pin "28") (pinfunction "IO35_28") (pintype "unspecified+no_connect"))
    )
    (net (code "67") (name "unconnected-(U6-IO36-Pad29)") (class "Default")
      (node (ref "U6") (pin "29") (pinfunction "IO36_29") (pintype "unspecified+no_connect"))
    )
    (net (code "68") (name "unconnected-(U6-IO37-Pad30)") (class "Default")
      (node (ref "U6") (pin "30") (pinfunction "IO37_30") (pintype "unspecified+no_connect"))
    )
    (net (code "69") (name "unconnected-(U6-IO40-Pad33)") (class "Default")
      (node (ref "U6") (pin "33") (pinfunction "IO40_33") (pintype "unspecified+no_connect"))
    )
    (net (code "70") (name "unconnected-(U6-IO45-Pad26)") (class "Default")
      (node (ref "U6") (pin "26") (pinfunction "IO45_26") (pintype "unspecified"))
    )
    (net (code "71") (name "unconnected-(U6-IO46-Pad16)") (class "Default")
      (node (ref "U6") (pin "16") (pinfunction "IO46_16") (pintype "unspecified+no_connect"))
    )
    (net (code "72") (name "unconnected-(U6-IO47-Pad24)") (class "Default")
      (node (ref "U6") (pin "24") (pinfunction "IO47_24") (pintype "unspecified"))
    )
    (net (code "73") (name "unconnected-(U6-IO48-Pad25)") (class "Default")
      (node (ref "U6") (pin "25") (pinfunction "IO48_25") (pintype "unspecified"))
    )
  )
)
